# W600A.net
KiCad netlist of a schematic drawn in EAGLE
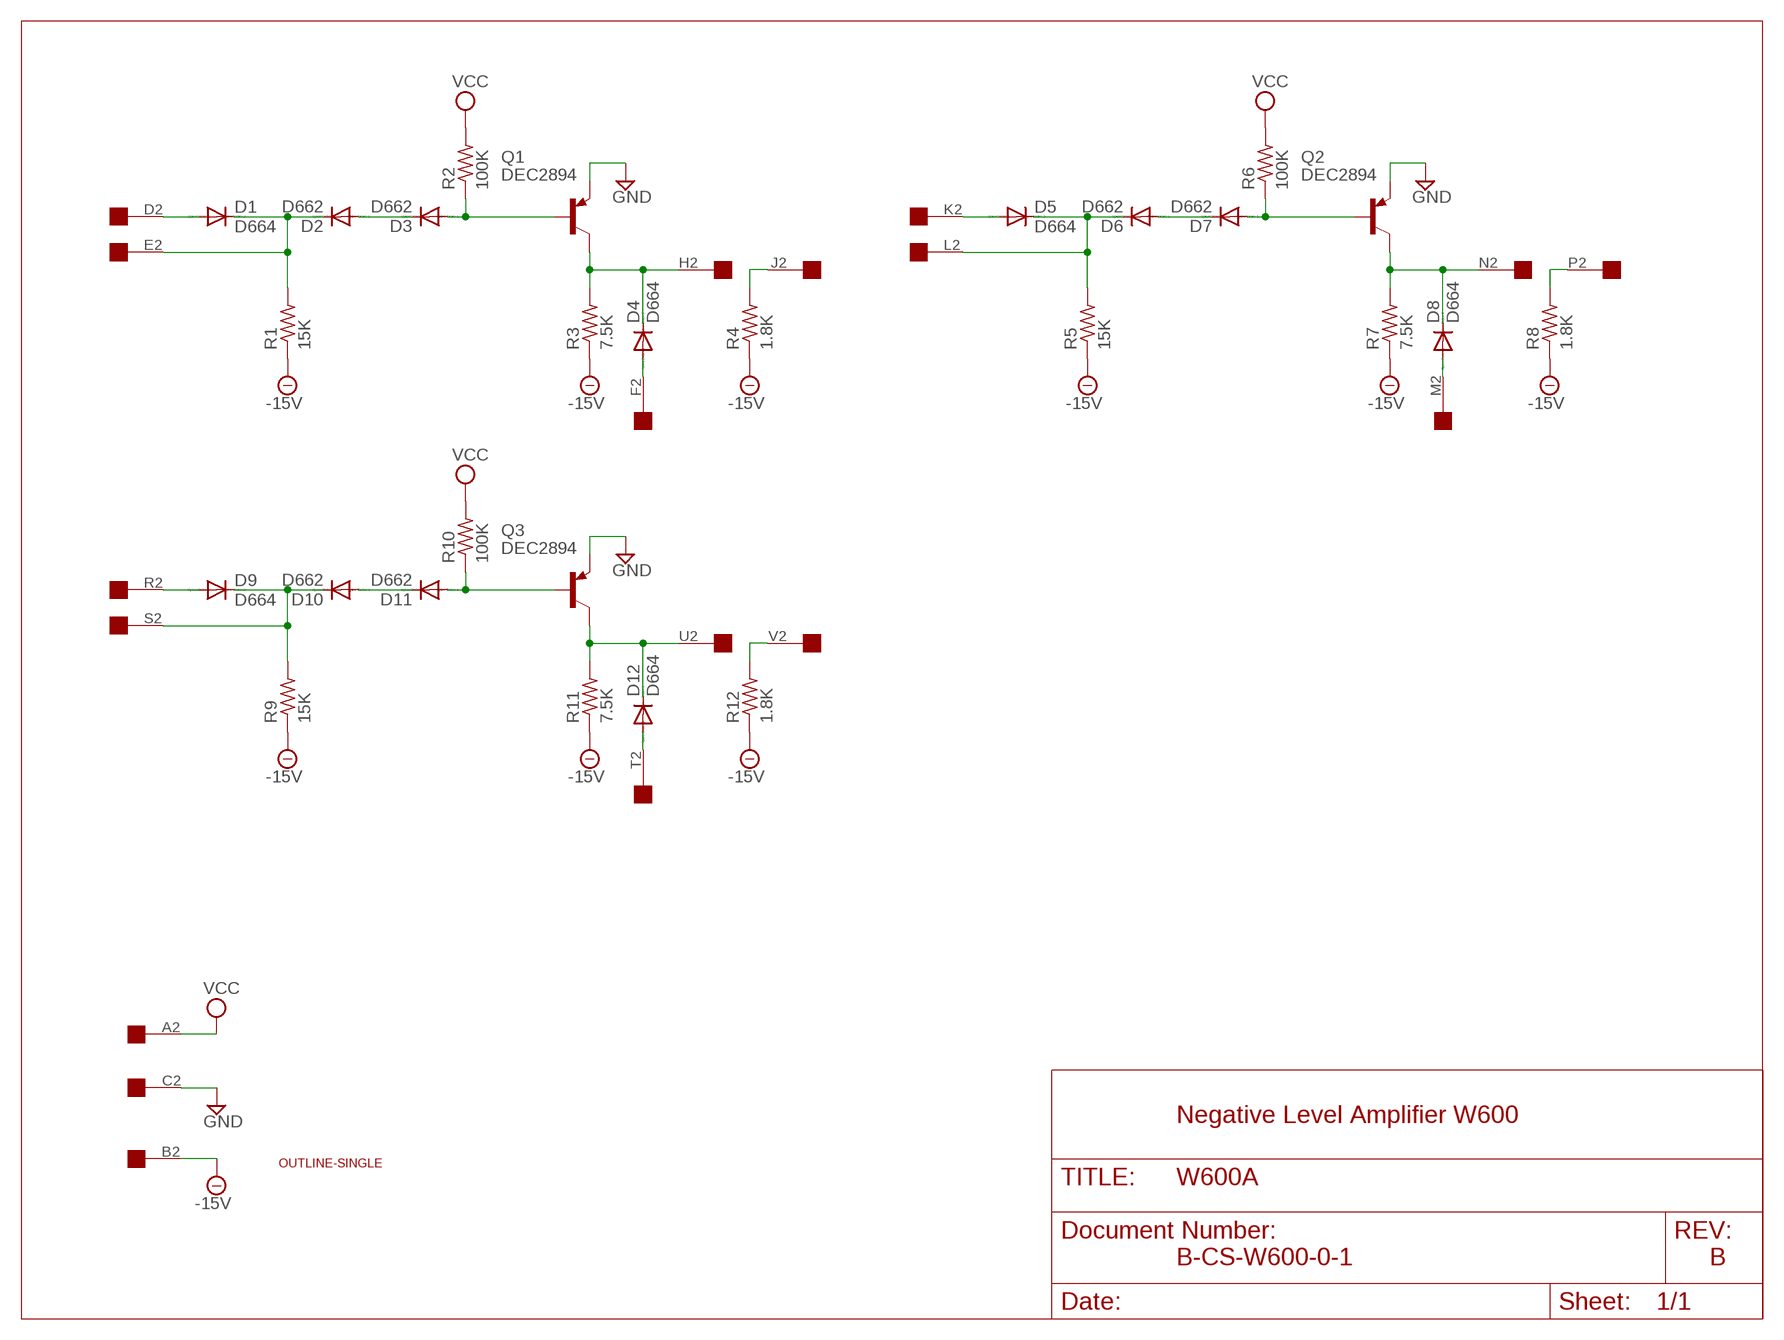
[diagram p0: schematic, sheet 1]

(export (version "E")
  (design (tool "Eeschema 10.0.6"))
  (components
    (comp (ref "D1")
      (value "D664")
      (footprint "eagle-import:DO35-10")
      (libsource (lib "eagle-import") (part "DIODE-DO35-10"))
    )
    (comp (ref "D2")
      (value "D662")
      (footprint "eagle-import:DO35-10")
      (libsource (lib "eagle-import") (part "DIODE-DO35-10"))
    )
    (comp (ref "D3")
      (value "D662")
      (footprint "eagle-import:DO35-10")
      (libsource (lib "eagle-import") (part "DIODE-DO35-10"))
    )
    (comp (ref "D4")
      (value "D664")
      (footprint "eagle-import:DO35-10")
      (libsource (lib "eagle-import") (part "DIODE-DO35-10"))
    )
    (comp (ref "D5")
      (value "D664")
      (footprint "eagle-import:DO35-10")
      (libsource (lib "eagle-import") (part "DIODE-DO35-10"))
    )
    (comp (ref "D6")
      (value "D662")
      (footprint "eagle-import:DO35-10")
      (libsource (lib "eagle-import") (part "DIODE-DO35-10"))
    )
    (comp (ref "D7")
      (value "D662")
      (footprint "eagle-import:DO35-10")
      (libsource (lib "eagle-import") (part "DIODE-DO35-10"))
    )
    (comp (ref "D8")
      (value "D664")
      (footprint "eagle-import:DO35-10")
      (libsource (lib "eagle-import") (part "DIODE-DO35-10"))
    )
    (comp (ref "D9")
      (value "D664")
      (footprint "eagle-import:DO35-10")
      (libsource (lib "eagle-import") (part "DIODE-DO35-10"))
    )
    (comp (ref "D10")
      (value "D662")
      (footprint "eagle-import:DO35-10")
      (libsource (lib "eagle-import") (part "DIODE-DO35-10"))
    )
    (comp (ref "D11")
      (value "D662")
      (footprint "eagle-import:DO35-10")
      (libsource (lib "eagle-import") (part "DIODE-DO35-10"))
    )
    (comp (ref "D12")
      (value "D664")
      (footprint "eagle-import:DO35-10")
      (libsource (lib "eagle-import") (part "DIODE-DO35-10"))
    )
    (comp (ref "Q1")
      (value "DEC2894")
      (footprint "eagle-import:TO5")
      (libsource (lib "eagle-import") (part "-PNP-TO5"))
    )
    (comp (ref "Q2")
      (value "DEC2894")
      (footprint "eagle-import:TO5")
      (libsource (lib "eagle-import") (part "-PNP-TO5"))
    )
    (comp (ref "Q3")
      (value "DEC2894")
      (footprint "eagle-import:TO5")
      (libsource (lib "eagle-import") (part "-PNP-TO5"))
    )
    (comp (ref "R1")
      (value "15K")
      (footprint "eagle-import:0207_10")
      (libsource (lib "eagle-import") (part "R-US_0207/10"))
    )
    (comp (ref "R2")
      (value "100K")
      (footprint "eagle-import:0207_10")
      (libsource (lib "eagle-import") (part "R-US_0207/10"))
    )
    (comp (ref "R3")
      (value "7.5K")
      (footprint "eagle-import:0207_10")
      (libsource (lib "eagle-import") (part "R-US_0207/10"))
    )
    (comp (ref "R4")
      (value "1.8K")
      (footprint "eagle-import:0207_10")
      (libsource (lib "eagle-import") (part "R-US_0207/10"))
    )
    (comp (ref "R5")
      (value "15K")
      (footprint "eagle-import:0207_10")
      (libsource (lib "eagle-import") (part "R-US_0207/10"))
    )
    (comp (ref "R6")
      (value "100K")
      (footprint "eagle-import:0207_10")
      (libsource (lib "eagle-import") (part "R-US_0207/10"))
    )
    (comp (ref "R7")
      (value "7.5K")
      (footprint "eagle-import:0207_10")
      (libsource (lib "eagle-import") (part "R-US_0207/10"))
    )
    (comp (ref "R8")
      (value "1.8K")
      (footprint "eagle-import:0207_10")
      (libsource (lib "eagle-import") (part "R-US_0207/10"))
    )
    (comp (ref "R9")
      (value "15K")
      (footprint "eagle-import:0207_10")
      (libsource (lib "eagle-import") (part "R-US_0207/10"))
    )
    (comp (ref "R10")
      (value "100K")
      (footprint "eagle-import:0207_10")
      (libsource (lib "eagle-import") (part "R-US_0207/10"))
    )
    (comp (ref "R11")
      (value "7.5K")
      (footprint "eagle-import:0207_10")
      (libsource (lib "eagle-import") (part "R-US_0207/10"))
    )
    (comp (ref "R12")
      (value "1.8K")
      (footprint "eagle-import:0207_10")
      (libsource (lib "eagle-import") (part "R-US_0207/10"))
    )
    (comp (ref "U$1")
      (value "OUTLINE-SINGLE")
      (footprint "eagle-import:SINGLE")
      (libsource (lib "eagle-import") (part "OUTLINE-SINGLE"))
    )
    (comp (ref "U$2")
      (value "EDGE-1")
      (footprint "eagle-import:EDGE-CON1")
      (libsource (lib "eagle-import") (part "EDGE-1"))
    )
  )
  (nets
    (net (code "1") (name "-15V") (class "Default")
      (node (ref "R1") (pin "1") (pinfunction "1_1") (pintype "passive"))
      (node (ref "R11") (pin "1") (pinfunction "1_1") (pintype "passive"))
      (node (ref "R12") (pin "1") (pinfunction "1_1") (pintype "passive"))
      (node (ref "R3") (pin "1") (pinfunction "1_1") (pintype "passive"))
      (node (ref "R4") (pin "1") (pinfunction "1_1") (pintype "passive"))
      (node (ref "R5") (pin "1") (pinfunction "1_1") (pintype "passive"))
      (node (ref "R7") (pin "1") (pinfunction "1_1") (pintype "passive"))
      (node (ref "R8") (pin "1") (pinfunction "1_1") (pintype "passive"))
      (node (ref "R9") (pin "1") (pinfunction "1_1") (pintype "passive"))
      (node (ref "U$2") (pin "B2") (pinfunction "1_B2") (pintype "bidirectional"))
    )
    (net (code "2") (name "GND") (class "Default")
      (node (ref "Q1") (pin "1") (pinfunction "E_1") (pintype "passive"))
      (node (ref "Q2") (pin "1") (pinfunction "E_1") (pintype "passive"))
      (node (ref "Q3") (pin "1") (pinfunction "E_1") (pintype "passive"))
      (node (ref "U$2") (pin "C2") (pinfunction "1_C2") (pintype "bidirectional"))
    )
    (net (code "3") (name "Net-(D2-PadA)") (class "Default")
      (node (ref "D2") (pin "A") (pinfunction "A_A") (pintype "passive"))
      (node (ref "D3") (pin "C") (pinfunction "C_C") (pintype "passive"))
    )
    (net (code "4") (name "Net-(D6-PadA)") (class "Default")
      (node (ref "D6") (pin "A") (pinfunction "A_A") (pintype "passive"))
      (node (ref "D7") (pin "C") (pinfunction "C_C") (pintype "passive"))
    )
    (net (code "5") (name "Net-(D10-PadA)") (class "Default")
      (node (ref "D10") (pin "A") (pinfunction "A_A") (pintype "passive"))
      (node (ref "D11") (pin "C") (pinfunction "C_C") (pintype "passive"))
    )
    (net (code "6") (name "Net-(Q1-B)") (class "Default")
      (node (ref "D3") (pin "A") (pinfunction "A_A") (pintype "passive"))
      (node (ref "Q1") (pin "2") (pinfunction "B_2") (pintype "passive"))
      (node (ref "R2") (pin "1") (pinfunction "1_1") (pintype "passive"))
    )
    (net (code "7") (name "Net-(Q1-C)") (class "Default")
      (node (ref "D4") (pin "C") (pinfunction "C_C") (pintype "passive"))
      (node (ref "Q1") (pin "3") (pinfunction "C_3") (pintype "passive"))
      (node (ref "R3") (pin "2") (pinfunction "2_2") (pintype "passive"))
      (node (ref "U$2") (pin "H2") (pinfunction "1_H2") (pintype "bidirectional"))
    )
    (net (code "8") (name "Net-(Q2-B)") (class "Default")
      (node (ref "D7") (pin "A") (pinfunction "A_A") (pintype "passive"))
      (node (ref "Q2") (pin "2") (pinfunction "B_2") (pintype "passive"))
      (node (ref "R6") (pin "1") (pinfunction "1_1") (pintype "passive"))
    )
    (net (code "9") (name "Net-(Q2-C)") (class "Default")
      (node (ref "D8") (pin "C") (pinfunction "C_C") (pintype "passive"))
      (node (ref "Q2") (pin "3") (pinfunction "C_3") (pintype "passive"))
      (node (ref "R7") (pin "2") (pinfunction "2_2") (pintype "passive"))
      (node (ref "U$2") (pin "N2") (pinfunction "1_N2") (pintype "bidirectional"))
    )
    (net (code "10") (name "Net-(Q3-B)") (class "Default")
      (node (ref "D11") (pin "A") (pinfunction "A_A") (pintype "passive"))
      (node (ref "Q3") (pin "2") (pinfunction "B_2") (pintype "passive"))
      (node (ref "R10") (pin "1") (pinfunction "1_1") (pintype "passive"))
    )
    (net (code "11") (name "Net-(Q3-C)") (class "Default")
      (node (ref "D12") (pin "C") (pinfunction "C_C") (pintype "passive"))
      (node (ref "Q3") (pin "3") (pinfunction "C_3") (pintype "passive"))
      (node (ref "R11") (pin "2") (pinfunction "2_2") (pintype "passive"))
      (node (ref "U$2") (pin "U2") (pinfunction "1_U2") (pintype "bidirectional"))
    )
    (net (code "12") (name "Net-(U$2D-1)") (class "Default")
      (node (ref "D1") (pin "A") (pinfunction "A_A") (pintype "passive"))
      (node (ref "U$2") (pin "D2") (pinfunction "1_D2") (pintype "bidirectional"))
    )
    (net (code "13") (name "Net-(U$2E-1)") (class "Default")
      (node (ref "D1") (pin "C") (pinfunction "C_C") (pintype "passive"))
      (node (ref "D2") (pin "C") (pinfunction "C_C") (pintype "passive"))
      (node (ref "R1") (pin "2") (pinfunction "2_2") (pintype "passive"))
      (node (ref "U$2") (pin "E2") (pinfunction "1_E2") (pintype "bidirectional"))
    )
    (net (code "14") (name "Net-(U$2F-1)") (class "Default")
      (node (ref "D4") (pin "A") (pinfunction "A_A") (pintype "passive"))
      (node (ref "U$2") (pin "F2") (pinfunction "1_F2") (pintype "bidirectional"))
    )
    (net (code "15") (name "Net-(U$2H-1)") (class "Default")
      (node (ref "R4") (pin "2") (pinfunction "2_2") (pintype "passive"))
      (node (ref "U$2") (pin "J2") (pinfunction "1_J2") (pintype "bidirectional"))
    )
    (net (code "16") (name "Net-(U$2I-1)") (class "Default")
      (node (ref "D5") (pin "A") (pinfunction "A_A") (pintype "passive"))
      (node (ref "U$2") (pin "K2") (pinfunction "1_K2") (pintype "bidirectional"))
    )
    (net (code "17") (name "Net-(U$2J-1)") (class "Default")
      (node (ref "D5") (pin "C") (pinfunction "C_C") (pintype "passive"))
      (node (ref "D6") (pin "C") (pinfunction "C_C") (pintype "passive"))
      (node (ref "R5") (pin "2") (pinfunction "2_2") (pintype "passive"))
      (node (ref "U$2") (pin "L2") (pinfunction "1_L2") (pintype "bidirectional"))
    )
    (net (code "18") (name "Net-(U$2K-1)") (class "Default")
      (node (ref "D8") (pin "A") (pinfunction "A_A") (pintype "passive"))
      (node (ref "U$2") (pin "M2") (pinfunction "1_M2") (pintype "bidirectional"))
    )
    (net (code "19") (name "Net-(U$2M-1)") (class "Default")
      (node (ref "R8") (pin "2") (pinfunction "2_2") (pintype "passive"))
      (node (ref "U$2") (pin "P2") (pinfunction "1_P2") (pintype "bidirectional"))
    )
    (net (code "20") (name "Net-(U$2N-1)") (class "Default")
      (node (ref "D9") (pin "A") (pinfunction "A_A") (pintype "passive"))
      (node (ref "U$2") (pin "R2") (pinfunction "1_R2") (pintype "bidirectional"))
    )
    (net (code "21") (name "Net-(U$2O-1)") (class "Default")
      (node (ref "D10") (pin "C") (pinfunction "C_C") (pintype "passive"))
      (node (ref "D9") (pin "C") (pinfunction "C_C") (pintype "passive"))
      (node (ref "R9") (pin "2") (pinfunction "2_2") (pintype "passive"))
      (node (ref "U$2") (pin "S2") (pinfunction "1_S2") (pintype "bidirectional"))
    )
    (net (code "22") (name "Net-(U$2P-1)") (class "Default")
      (node (ref "D12") (pin "A") (pinfunction "A_A") (pintype "passive"))
      (node (ref "U$2") (pin "T2") (pinfunction "1_T2") (pintype "bidirectional"))
    )
    (net (code "23") (name "Net-(U$2R-1)") (class "Default")
      (node (ref "R12") (pin "2") (pinfunction "2_2") (pintype "passive"))
      (node (ref "U$2") (pin "V2") (pinfunction "1_V2") (pintype "bidirectional"))
    )
    (net (code "24") (name "VCC") (class "Default")
      (node (ref "R10") (pin "2") (pinfunction "2_2") (pintype "passive"))
      (node (ref "R2") (pin "2") (pinfunction "2_2") (pintype "passive"))
      (node (ref "R6") (pin "2") (pinfunction "2_2") (pintype "passive"))
      (node (ref "U$2") (pin "A2") (pinfunction "1_A2") (pintype "bidirectional"))
    )
  )
)
